# 2_-PMUIO_BLOCK.net
KiCad netlist of a schematic drawn in Altium Designer
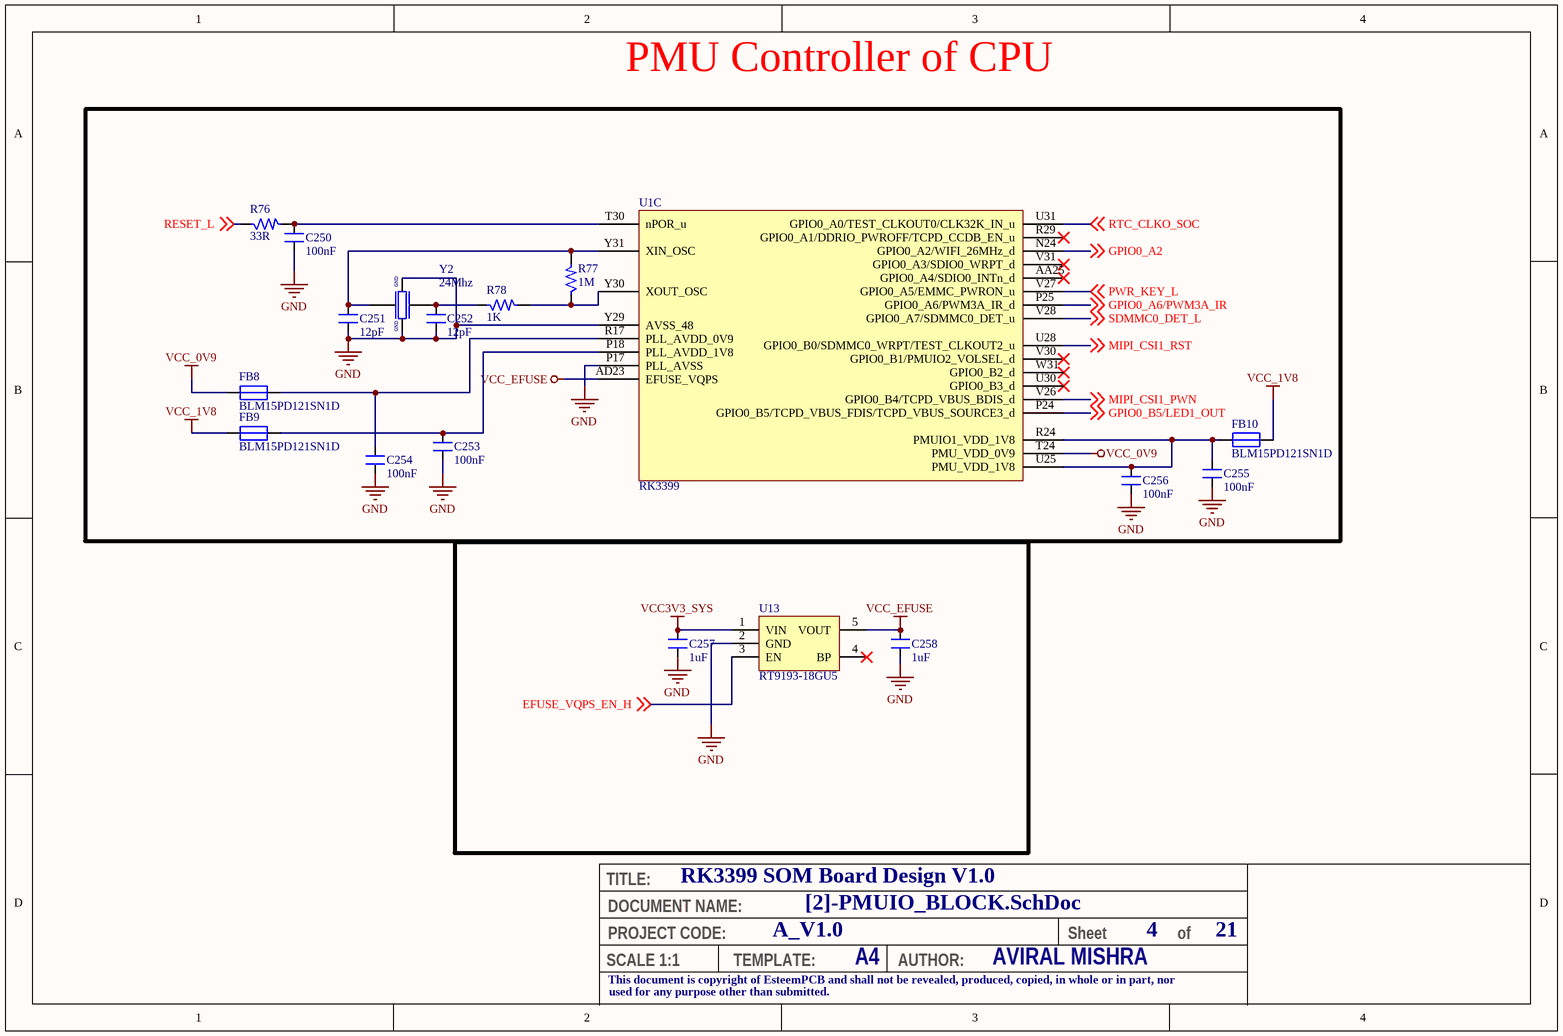
[diagram p0: [2]-PMUIO_BLOCK.SchDoc]

(export (version "E")
  (design (tool "Eeschema 10.0.6"))
  (components
    (comp (ref "C250")
      (value "100nF")
      (footprint "CAP_0201")
      (description "0.1µF ±10% 25V Ceramic Capacitor X5R 0201 (0603 Metric)")
      (fields
        (field (name "MANUFACTURER") "TDK Corporation")
        (field (name "MANUFACTURER PART NUMBER") "C0603X5R1E104K030BB")
      )
      (libsource (lib "RK3399 _Module_Intlib") (part "CAP_100nF-25V-10%-0201"))
    )
    (comp (ref "C251")
      (value "12pF")
      (footprint "CAP_0201")
      (description "12pF ±10% 16V Ceramic Capacitor C0G, NP0 0201 (0603 Metric)")
      (fields
        (field (name "MANUFACTURER") "AVX Corporation")
        (field (name "MANUFACTURER PART NUMBER") "0201YA120KAT2A")
      )
      (libsource (lib "RK3399 _Module_Intlib") (part "CAP_12pF-16V-10%-0201"))
    )
    (comp (ref "C252")
      (value "12pF")
      (footprint "CAP_0201")
      (description "12pF ±10% 16V Ceramic Capacitor C0G, NP0 0201 (0603 Metric)")
      (fields
        (field (name "MANUFACTURER") "AVX Corporation")
        (field (name "MANUFACTURER PART NUMBER") "0201YA120KAT2A")
      )
      (libsource (lib "RK3399 _Module_Intlib") (part "CAP_12pF-16V-10%-0201"))
    )
    (comp (ref "C253")
      (value "100nF")
      (footprint "CAP_0201")
      (description "0.1µF ±10% 25V Ceramic Capacitor X5R 0201 (0603 Metric)")
      (fields
        (field (name "MANUFACTURER") "TDK Corporation")
        (field (name "MANUFACTURER PART NUMBER") "C0603X5R1E104K030BB")
      )
      (libsource (lib "RK3399 _Module_Intlib") (part "CAP_100nF-25V-10%-0201"))
    )
    (comp (ref "C254")
      (value "100nF")
      (footprint "CAP_0201")
      (description "0.1µF ±10% 25V Ceramic Capacitor X5R 0201 (0603 Metric)")
      (fields
        (field (name "MANUFACTURER") "TDK Corporation")
        (field (name "MANUFACTURER PART NUMBER") "C0603X5R1E104K030BB")
      )
      (libsource (lib "RK3399 _Module_Intlib") (part "CAP_100nF-25V-10%-0201"))
    )
    (comp (ref "C255")
      (value "100nF")
      (footprint "CAP_0201")
      (description "0.1µF ±10% 25V Ceramic Capacitor X5R 0201 (0603 Metric)")
      (fields
        (field (name "MANUFACTURER") "TDK Corporation")
        (field (name "MANUFACTURER PART NUMBER") "C0603X5R1E104K030BB")
      )
      (libsource (lib "RK3399 _Module_Intlib") (part "CAP_100nF-25V-10%-0201"))
    )
    (comp (ref "C256")
      (value "100nF")
      (footprint "CAP_0201")
      (description "0.1µF ±10% 25V Ceramic Capacitor X5R 0201 (0603 Metric)")
      (fields
        (field (name "MANUFACTURER") "TDK Corporation")
        (field (name "MANUFACTURER PART NUMBER") "C0603X5R1E104K030BB")
      )
      (libsource (lib "RK3399 _Module_Intlib") (part "CAP_100nF-25V-10%-0201"))
    )
    (comp (ref "C257")
      (value "1uF")
      (footprint "CAP_0201")
      (description "1µF ±20% 16V Ceramic Capacitor X5R 0201 (0603 Metric)")
      (fields
        (field (name "MANUFACTURER") "Samsung Electro-Mechanics")
        (field (name "MANUFACTURER PART NUMBER") "CL03A105MO3NRNH")
      )
      (libsource (lib "RK3399 _Module_Intlib") (part "CAP_1uF-16V-10%-0201"))
    )
    (comp (ref "C258")
      (value "1uF")
      (footprint "CAP_0201")
      (description "1µF ±20% 16V Ceramic Capacitor X5R 0201 (0603 Metric)")
      (fields
        (field (name "MANUFACTURER") "Samsung Electro-Mechanics")
        (field (name "MANUFACTURER PART NUMBER") "CL03A105MO3NRNH")
      )
      (libsource (lib "RK3399 _Module_Intlib") (part "CAP_1uF-16V-10%-0201"))
    )
    (comp (ref "FB8")
      (value "BLM15PD121SN1D")
      (footprint "RES_0402")
      (description "120 Ohms @ 100MHz 1 Power Line Ferrite Bead 0402 (1005 Metric) 1.3A 90mOhm")
      (fields (field (name "MANUFACTURER") "Murata Electronics"))
      (libsource (lib "RK3399 _Module_Schlib") (part "FB_120R-1.3A-100Mhz-0402"))
    )
    (comp (ref "FB9")
      (value "BLM15PD121SN1D")
      (footprint "RES_0402")
      (description "120 Ohms @ 100MHz 1 Power Line Ferrite Bead 0402 (1005 Metric) 1.3A 90mOhm")
      (fields (field (name "MANUFACTURER") "Murata Electronics"))
      (libsource (lib "RK3399 _Module_Schlib") (part "FB_120R-1.3A-100Mhz-0402"))
    )
    (comp (ref "FB10")
      (value "BLM15PD121SN1D")
      (footprint "RES_0402")
      (description "120 Ohms @ 100MHz 1 Power Line Ferrite Bead 0402 (1005 Metric) 1.3A 90mOhm")
      (fields (field (name "MANUFACTURER") "Murata Electronics"))
      (libsource (lib "RK3399 _Module_Schlib") (part "FB_120R-1.3A-100Mhz-0402"))
    )
    (comp (ref "R76")
      (value "33R")
      (footprint "RES_0201")
      (description "33 Ohms ±1% 0.05W, 1/20W Chip Resistor 0201 (0603 Metric) Thick Film")
      (fields
        (field (name "MANUFACTURER") "Yageo")
        (field (name "MANUFACTURER PART NUMBER") "RC0201FR-0733RL")
      )
      (libsource (lib "RK3399 _Module_Intlib") (part "RES_33R-0.05W-1%-0201"))
    )
    (comp (ref "R77")
      (value "1M")
      (footprint "RES_0201")
      (description "1 MOhms ±1% 0.05W, 1/20W Chip Resistor 0201 (0603 Metric) Thick Film")
      (fields
        (field (name "MANUFACTURER") "Yageo")
        (field (name "MANUFACTURER PART NUMBER") "RC0201FR-071ML")
      )
      (libsource (lib "RK3399 _Module_Intlib") (part "RES_1M-0.05W-1%-0201"))
    )
    (comp (ref "R78")
      (value "1K")
      (footprint "RES_0201")
      (description "1 kOhms ±1% 0.05W, 1/20W Chip Resistor 0201 (0603 Metric) Thick Film")
      (fields
        (field (name "MANUFACTURER") "Yageo")
        (field (name "MANUFACTURER PART NUMBER") "RC0201FR-071KL")
      )
      (libsource (lib "RK3399 _Module_Intlib") (part "RES_1K-0.05W-1%-0201"))
    )
    (comp (ref "U1")
      (value "RK3399")
      (footprint "FBGA828_23_826X826")
      (description "RK3399 is a low power, high performance processor for computing, personal mobile.")
      (fields (field (name "MANUFACTURER") "Rockchip"))
      (libsource (lib "RK3399 _Module_Schlib") (part "IC_RK3399-FCBGA828"))
    )
    (comp (ref "U13")
      (value "RT9193-18GU5")
      (footprint "SC70-5")
      (description "Linear Voltage Regulator IC 1 Output 300mA SC-70-5")
      (fields (field (name "MANUFACTURER") "Richtek USA Inc."))
      (libsource (lib "RK3399 _Module_Schlib") (part "REG_1.8V-300mA-5.5V-SC70-5"))
    )
    (comp (ref "Y2")
      (value "24Mhz")
      (footprint "XTAL_ABM8AIG-24.000MHZ-12-2Z-T3")
      (description "24MHz ±20ppm Crystal 12pF 50 Ohms 4-SMD, No Lead")
      (fields
        (field (name "MANUFACTURER") "Abracon LLC")
        (field (name "MANUFACTURER PART NUMBER") "ABM8AIG-24.000MHZ-12-2Z-T3")
      )
      (libsource (lib "RK3399 _Module_Schlib") (part "XTAL_24Mhz-12pF-4-SMD"))
    )
  )
  (nets
    (net (code "1") (name "EFUSE_VQPS_EN_H") (class "Default")
      (node (ref "U13") (pin "3") (pinfunction "EN_3") (pintype "passive"))
    )
    (net (code "2") (name "GND") (class "Default")
      (node (ref "C250") (pin "1") (pinfunction "1_1") (pintype "passive"))
      (node (ref "C251") (pin "1") (pinfunction "1_1") (pintype "passive"))
      (node (ref "C252") (pin "1") (pinfunction "1_1") (pintype "passive"))
      (node (ref "C253") (pin "1") (pinfunction "1_1") (pintype "passive"))
      (node (ref "C254") (pin "1") (pinfunction "1_1") (pintype "passive"))
      (node (ref "C255") (pin "1") (pinfunction "1_1") (pintype "passive"))
      (node (ref "C256") (pin "1") (pinfunction "1_1") (pintype "passive"))
      (node (ref "C257") (pin "1") (pinfunction "1_1") (pintype "passive"))
      (node (ref "C258") (pin "1") (pinfunction "1_1") (pintype "passive"))
      (node (ref "U1") (pin "P17") (pinfunction "PLL_AVSS_P17") (pintype "passive"))
      (node (ref "U1") (pin "Y29") (pinfunction "AVSS_48_Y29") (pintype "passive"))
      (node (ref "U13") (pin "2") (pinfunction "GND_2") (pintype "passive"))
      (node (ref "Y2") (pin "2") (pinfunction "2_2") (pintype "passive"))
      (node (ref "Y2") (pin "4") (pinfunction "4_4") (pintype "passive"))
    )
    (net (code "3") (name "GPIO0_A2") (class "Default")
      (node (ref "U1") (pin "N24") (pinfunction "GPIO0_A2/WIFI_26MHz_d_N24") (pintype "passive"))
    )
    (net (code "4") (name "GPIO0_A6{slash}PWM3A_IR") (class "Default")
      (node (ref "U1") (pin "P25") (pinfunction "GPIO0_A6/PWM3A_IR_d_P25") (pintype "passive"))
    )
    (net (code "5") (name "GPIO0_B5{slash}LED1_OUT") (class "Default")
      (node (ref "U1") (pin "P24") (pinfunction "GPIO0_B5/TCPD_VBUS_FDIS/TCPD_VBUS_SOURCE3_d_P24") (pintype "passive"))
    )
    (net (code "6") (name "MIPI_CSI1_PWN") (class "Default")
      (node (ref "U1") (pin "V26") (pinfunction "GPIO0_B4/TCPD_VBUS_BDIS_d_V26") (pintype "passive"))
    )
    (net (code "7") (name "MIPI_CSI1_RST") (class "Default")
      (node (ref "U1") (pin "U28") (pinfunction "GPIO0_B0/SDMMC0_WRPT/TEST_CLKOUT2_u_U28") (pintype "passive"))
    )
    (net (code "8") (name "Net-(C252-Pad2)") (class "Default")
      (node (ref "C252") (pin "2") (pinfunction "2_2") (pintype "passive"))
      (node (ref "R78") (pin "1") (pinfunction "1_1") (pintype "passive"))
      (node (ref "Y2") (pin "3") (pinfunction "3_3") (pintype "passive"))
    )
    (net (code "9") (name "Net-(U1C-PLL_AVDD_0V9)") (class "Default")
      (node (ref "C254") (pin "2") (pinfunction "2_2") (pintype "passive"))
      (node (ref "FB8") (pin "2") (pinfunction "2_2") (pintype "passive"))
      (node (ref "U1") (pin "R17") (pinfunction "PLL_AVDD_0V9_R17") (pintype "passive"))
    )
    (net (code "10") (name "Net-(U1C-PLL_AVDD_1V8)") (class "Default")
      (node (ref "C253") (pin "2") (pinfunction "2_2") (pintype "passive"))
      (node (ref "FB9") (pin "2") (pinfunction "2_2") (pintype "passive"))
      (node (ref "U1") (pin "P18") (pinfunction "PLL_AVDD_1V8_P18") (pintype "passive"))
    )
    (net (code "11") (name "Net-(U1C-PMUIO1_VDD_1V8)") (class "Default")
      (node (ref "C255") (pin "2") (pinfunction "2_2") (pintype "passive"))
      (node (ref "C256") (pin "2") (pinfunction "2_2") (pintype "passive"))
      (node (ref "FB10") (pin "1") (pinfunction "1_1") (pintype "passive"))
      (node (ref "U1") (pin "R24") (pinfunction "PMUIO1_VDD_1V8_R24") (pintype "passive"))
      (node (ref "U1") (pin "U25") (pinfunction "PMU_VDD_1V8_U25") (pintype "passive"))
    )
    (net (code "12") (name "Net-(U1C-XIN_OSC)") (class "Default")
      (node (ref "C251") (pin "2") (pinfunction "2_2") (pintype "passive"))
      (node (ref "R77") (pin "2") (pinfunction "2_2") (pintype "passive"))
      (node (ref "U1") (pin "Y31") (pinfunction "XIN_OSC_Y31") (pintype "passive"))
      (node (ref "Y2") (pin "1") (pinfunction "1_1") (pintype "passive"))
    )
    (net (code "13") (name "Net-(U1C-XOUT_OSC)") (class "Default")
      (node (ref "R77") (pin "1") (pinfunction "1_1") (pintype "passive"))
      (node (ref "R78") (pin "2") (pinfunction "2_2") (pintype "passive"))
      (node (ref "U1") (pin "Y30") (pinfunction "XOUT_OSC_Y30") (pintype "passive"))
    )
    (net (code "14") (name "Net-(U1C-nPOR_u)") (class "Default")
      (node (ref "C250") (pin "2") (pinfunction "2_2") (pintype "passive"))
      (node (ref "R76") (pin "2") (pinfunction "2_2") (pintype "passive"))
      (node (ref "U1") (pin "T30") (pinfunction "nPOR_u_T30") (pintype "passive"))
    )
    (net (code "15") (name "PWR_KEY_L") (class "Default")
      (node (ref "U1") (pin "V27") (pinfunction "GPIO0_A5/EMMC_PWRON_u_V27") (pintype "passive"))
    )
    (net (code "16") (name "RESET_L") (class "Default")
      (node (ref "R76") (pin "1") (pinfunction "1_1") (pintype "passive"))
    )
    (net (code "17") (name "RTC_CLKO_SOC") (class "Default")
      (node (ref "U1") (pin "U31") (pinfunction "GPIO0_A0/TEST_CLKOUT0/CLK32K_IN_u_U31") (pintype "passive"))
    )
    (net (code "18") (name "SDMMC0_DET_L") (class "Default")
      (node (ref "U1") (pin "V28") (pinfunction "GPIO0_A7/SDMMC0_DET_u_V28") (pintype "passive"))
    )
    (net (code "19") (name "VCC3V3_SYS") (class "Default")
      (node (ref "C257") (pin "2") (pinfunction "2_2") (pintype "passive"))
      (node (ref "U13") (pin "1") (pinfunction "VIN_1") (pintype "passive"))
    )
    (net (code "20") (name "VCC_0V9") (class "Default")
      (node (ref "FB8") (pin "1") (pinfunction "1_1") (pintype "passive"))
      (node (ref "U1") (pin "T24") (pinfunction "PMU_VDD_0V9_T24") (pintype "passive"))
    )
    (net (code "21") (name "VCC_1V8") (class "Default")
      (node (ref "FB10") (pin "2") (pinfunction "2_2") (pintype "passive"))
      (node (ref "FB9") (pin "1") (pinfunction "1_1") (pintype "passive"))
    )
    (net (code "22") (name "VCC_EFUSE") (class "Default")
      (node (ref "C258") (pin "2") (pinfunction "2_2") (pintype "passive"))
      (node (ref "U1") (pin "AD23") (pinfunction "EFUSE_VQPS_AD23") (pintype "passive"))
      (node (ref "U13") (pin "5") (pinfunction "VOUT_5") (pintype "passive"))
    )
    (net (code "23") (name "unconnected-(U1C-GPIO0_A1{slash}DDRIO_PWROFF{slash}TCPD_CCDB_EN_u-PadR29)") (class "Default")
      (node (ref "U1") (pin "R29") (pinfunction "GPIO0_A1/DDRIO_PWROFF/TCPD_CCDB_EN_u_R29") (pintype "passive+no_connect"))
    )
    (net (code "24") (name "unconnected-(U1C-GPIO0_A3{slash}SDIO0_WRPT_d-PadV31)") (class "Default")
      (node (ref "U1") (pin "V31") (pinfunction "GPIO0_A3/SDIO0_WRPT_d_V31") (pintype "passive+no_connect"))
    )
    (net (code "25") (name "unconnected-(U1C-GPIO0_A4{slash}SDIO0_INTn_d-PadAA25)") (class "Default")
      (node (ref "U1") (pin "AA25") (pinfunction "GPIO0_A4/SDIO0_INTn_d_AA25") (pintype "passive+no_connect"))
    )
    (net (code "26") (name "unconnected-(U1C-GPIO0_B1{slash}PMUIO2_VOLSEL_d-PadV30)") (class "Default")
      (node (ref "U1") (pin "V30") (pinfunction "GPIO0_B1/PMUIO2_VOLSEL_d_V30") (pintype "passive+no_connect"))
    )
    (net (code "27") (name "unconnected-(U1C-GPIO0_B2_d-PadW31)") (class "Default")
      (node (ref "U1") (pin "W31") (pinfunction "GPIO0_B2_d_W31") (pintype "passive+no_connect"))
    )
    (net (code "28") (name "unconnected-(U1C-GPIO0_B3_d-PadU30)") (class "Default")
      (node (ref "U1") (pin "U30") (pinfunction "GPIO0_B3_d_U30") (pintype "passive+no_connect"))
    )
    (net (code "29") (name "unconnected-(U13-BP-Pad4)") (class "Default")
      (node (ref "U13") (pin "4") (pinfunction "BP_4") (pintype "passive+no_connect"))
    )
  )
)
